# PrototypeBoardV1B.net
KiCad netlist of a schematic drawn in EasyEDA Pro
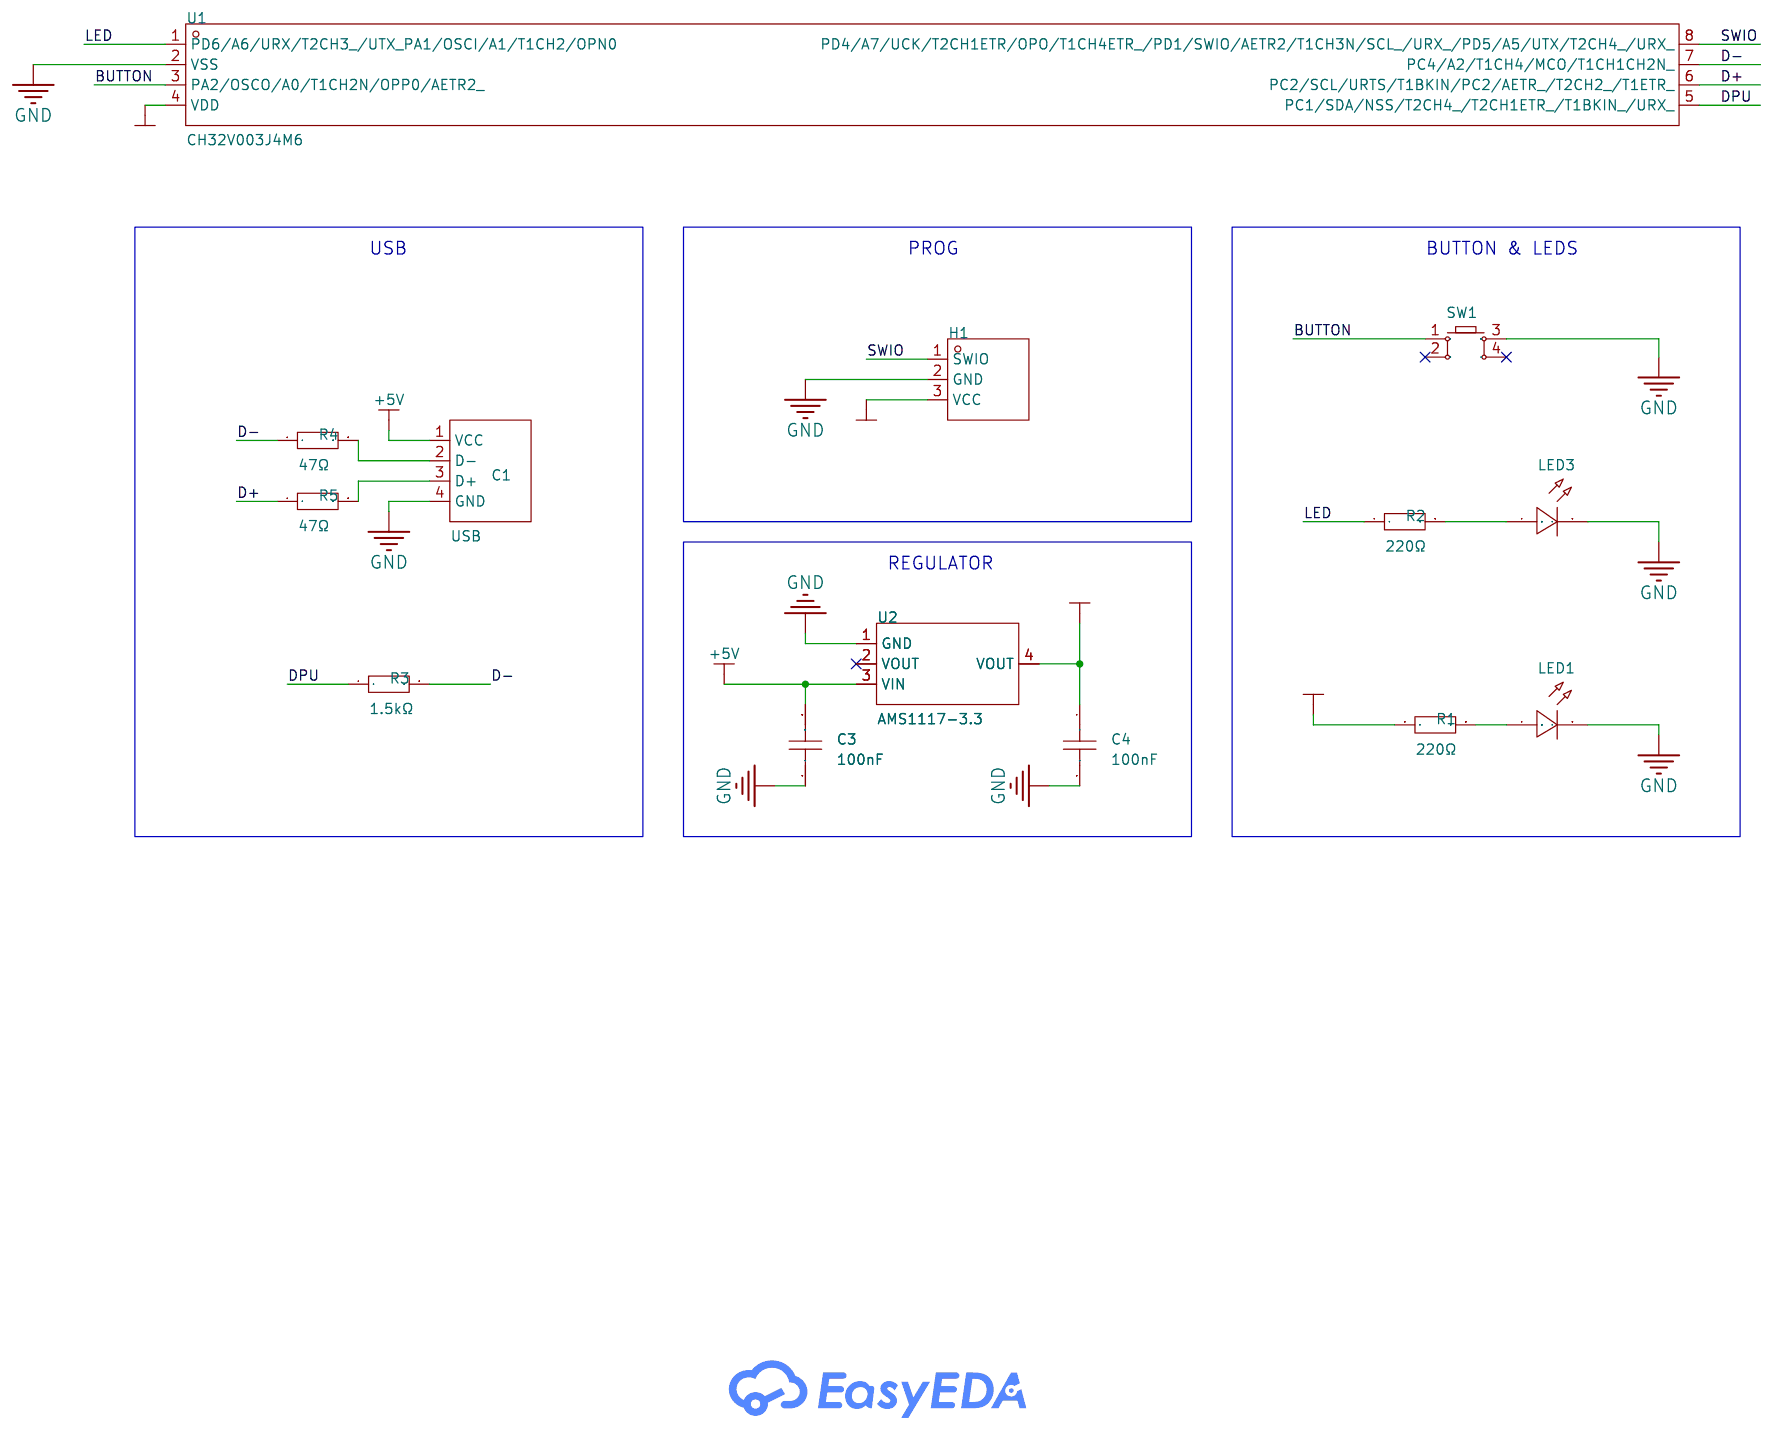
[diagram p0: schematic sheet]

(export (version "E")
  (design (tool "Eeschema 10.0.6"))
  (components
    (comp (ref "C1")
      (value "USB")
      (footprint "easyedapro:USB Type-C 4P")
      (libsource (lib "easyedapro") (part "USB Type-C 4P Board"))
    )
    (comp (ref "C3")
      (value "100nF")
      (footprint "easyedapro:CAP-TH_L5.8-W3.0-P4.7-D0.45")
      (fields (field (name "Manufacturer Part") "1C10Z5U104M050B") (field (name "Manufacturer") "VISHAY(威世)"))
      (libsource (lib "easyedapro") (part "1C10Z5U104M050B"))
    )
    (comp (ref "C4")
      (value "100nF")
      (footprint "easyedapro:CAP-TH_L5.8-W3.0-P4.7-D0.45")
      (fields (field (name "Manufacturer Part") "1C10Z5U104M050B") (field (name "Manufacturer") "VISHAY(威世)"))
      (libsource (lib "easyedapro") (part "1C10Z5U104M050B"))
    )
    (comp (ref "H1")
      (value "~")
      (footprint "easyedapro:HDR-TH_3P-P2.54-V-M")
      (libsource (lib "easyedapro") (part "PZ254V-11-03P_C2937625"))
    )
    (comp (ref "LED1")
      (value "~")
      (footprint "easyedapro:LED-TH_BD3.0-P2.54-FD")
      (libsource (lib "easyedapro") (part "LED_TH-R"))
    )
    (comp (ref "LED3")
      (value "~")
      (footprint "easyedapro:LED-TH_BD5.0-P2.54-L-RD_WHITE")
      (libsource (lib "easyedapro") (part "LED_TH-B"))
    )
    (comp (ref "R1")
      (value "220Ω")
      (footprint "easyedapro:RES-TH_BD1.8-L3.2-P7.20-D0.4")
      (libsource (lib "easyedapro") (part "Res"))
    )
    (comp (ref "R2")
      (value "220Ω")
      (footprint "easyedapro:RES-TH_BD1.8-L3.2-P7.20-D0.4")
      (libsource (lib "easyedapro") (part "Res"))
    )
    (comp (ref "R3")
      (value "1.5kΩ")
      (footprint "easyedapro:RES-TH_BD1.8-L3.2-P7.20-D0.4")
      (libsource (lib "easyedapro") (part "Res"))
    )
    (comp (ref "R4")
      (value "47Ω")
      (footprint "easyedapro:RES-TH_BD1.8-L3.2-P7.20-D0.4")
      (libsource (lib "easyedapro") (part "Res"))
    )
    (comp (ref "R5")
      (value "47Ω")
      (footprint "easyedapro:RES-TH_BD1.8-L3.2-P7.20-D0.4")
      (libsource (lib "easyedapro") (part "Res"))
    )
    (comp (ref "SW1")
      (value "~")
      (footprint "easyedapro:KEY-TH_4P-L6.0-W6.0-P3.90-LS6.5")
      (libsource (lib "easyedapro") (part "轻触按键"))
    )
    (comp (ref "U1")
      (value "CH32V003J4M6")
      (footprint "easyedapro:SOP-8_L4.9-W3.8-P1.27-LS6.0-BL")
      (fields (field (name "Manufacturer") "WCH(南京沁恒)"))
      (libsource (lib "easyedapro") (part "CH32V003J4M6_C5346354"))
    )
    (comp (ref "U2")
      (value "AMS1117-3.3")
      (footprint "easyedapro:SOT-223-3_L6.5-W3.4-P2.30-LS7.0-BR")
      (fields (field (name "Manufacturer") "AMS"))
      (libsource (lib "easyedapro") (part "AMS1117-3.3"))
    )
  )
  (nets
    (net (code "1") (name "+3.3V") (class "Default")
      (node (ref "C4") (pin "1") (pinfunction "1_1") (pintype "unspecified"))
      (node (ref "H1") (pin "3") (pinfunction "VCC_3") (pintype "unspecified"))
      (node (ref "R1") (pin "1") (pinfunction "1_1") (pintype "input"))
      (node (ref "U1") (pin "4") (pinfunction "VDD_4") (pintype "unspecified"))
      (node (ref "U2") (pin "4") (pinfunction "VOUT_4") (pintype "unspecified"))
    )
    (net (code "2") (name "+5V") (class "Default")
      (node (ref "C1") (pin "1") (pinfunction "VCC_1") (pintype "input"))
      (node (ref "C3") (pin "2") (pinfunction "2_2") (pintype "unspecified"))
      (node (ref "U2") (pin "3") (pinfunction "VIN_3") (pintype "unspecified"))
    )
    (net (code "3") (name "/BUTTON") (class "Default")
      (node (ref "SW1") (pin "1") (pinfunction "1_1") (pintype "input"))
      (node (ref "U1") (pin "3") (pinfunction "PA2/OSCO/A0/T1CH2N/OPP0/AETR2__3") (pintype "unspecified"))
    )
    (net (code "4") (name "/D+") (class "Default")
      (node (ref "R5") (pin "1") (pinfunction "1_1") (pintype "input"))
      (node (ref "U1") (pin "6") (pinfunction "PC2/SCL/URTS/T1BKIN/PC2/AETR_/T2CH2_/T1ETR__6") (pintype "unspecified"))
    )
    (net (code "5") (name "/D-") (class "Default")
      (node (ref "R3") (pin "2") (pinfunction "2_2") (pintype "input"))
      (node (ref "R4") (pin "1") (pinfunction "1_1") (pintype "input"))
      (node (ref "U1") (pin "7") (pinfunction "PC4/A2/T1CH4/MCO/T1CH1CH2N__7") (pintype "unspecified"))
    )
    (net (code "6") (name "/DPU") (class "Default")
      (node (ref "R3") (pin "1") (pinfunction "1_1") (pintype "input"))
      (node (ref "U1") (pin "5") (pinfunction "PC1/SDA/NSS/T2CH4_/T2CH1ETR_/T1BKIN_/URX__5") (pintype "unspecified"))
    )
    (net (code "7") (name "/LED") (class "Default")
      (node (ref "R2") (pin "1") (pinfunction "1_1") (pintype "input"))
      (node (ref "U1") (pin "1") (pinfunction "PD6/A6/URX/T2CH3_/UTX_PA1/OSCI/A1/T1CH2/OPN0_1") (pintype "unspecified"))
    )
    (net (code "8") (name "/SWIO") (class "Default")
      (node (ref "H1") (pin "1") (pinfunction "SWIO_1") (pintype "unspecified"))
      (node (ref "U1") (pin "8") (pinfunction "PD4/A7/UCK/T2CH1ETR/OPO/T1CH4ETR_/PD1/SWIO/AETR2/T1CH3N/SCL_/URX_/PD5/A5/UTX/T2CH4_/URX__8") (pintype "unspecified"))
    )
    (net (code "9") (name "GND") (class "Default")
      (node (ref "C1") (pin "4") (pinfunction "GND_4") (pintype "input"))
      (node (ref "C3") (pin "1") (pinfunction "1_1") (pintype "unspecified"))
      (node (ref "C4") (pin "2") (pinfunction "2_2") (pintype "unspecified"))
      (node (ref "H1") (pin "2") (pinfunction "GND_2") (pintype "unspecified"))
      (node (ref "LED1") (pin "2") (pinfunction "A_2") (pintype "input"))
      (node (ref "LED3") (pin "2") (pinfunction "A_2") (pintype "input"))
      (node (ref "SW1") (pin "3") (pinfunction "3_3") (pintype "input"))
      (node (ref "U1") (pin "2") (pinfunction "VSS_2") (pintype "unspecified"))
      (node (ref "U2") (pin "1") (pinfunction "GND_1") (pintype "unspecified"))
    )
    (net (code "10") (name "Net-(C1-D+)") (class "Default")
      (node (ref "C1") (pin "3") (pinfunction "D+_3") (pintype "input"))
      (node (ref "R5") (pin "2") (pinfunction "2_2") (pintype "input"))
    )
    (net (code "11") (name "Net-(C1-D-)") (class "Default")
      (node (ref "C1") (pin "2") (pinfunction "D-_2") (pintype "input"))
      (node (ref "R4") (pin "2") (pinfunction "2_2") (pintype "input"))
    )
    (net (code "12") (name "Net-(LED1-C)") (class "Default")
      (node (ref "LED1") (pin "1") (pinfunction "C_1") (pintype "input"))
      (node (ref "R1") (pin "2") (pinfunction "2_2") (pintype "input"))
    )
    (net (code "13") (name "Net-(LED3-C)") (class "Default")
      (node (ref "LED3") (pin "1") (pinfunction "C_1") (pintype "input"))
      (node (ref "R2") (pin "2") (pinfunction "2_2") (pintype "input"))
    )
    (net (code "14") (name "unconnected-(SW1-Pad2)") (class "Default")
      (node (ref "SW1") (pin "2") (pinfunction "2_2") (pintype "input+no_connect"))
    )
    (net (code "15") (name "unconnected-(SW1-Pad4)") (class "Default")
      (node (ref "SW1") (pin "4") (pinfunction "4_4") (pintype "input+no_connect"))
    )
    (net (code "16") (name "unconnected-(U2-VOUT-Pad2)") (class "Default")
      (node (ref "U2") (pin "2") (pinfunction "VOUT_2") (pintype "unspecified+no_connect"))
    )
  )
)
